# TrinketBlinkM0E.net
KiCad netlist of a schematic drawn in EAGLE
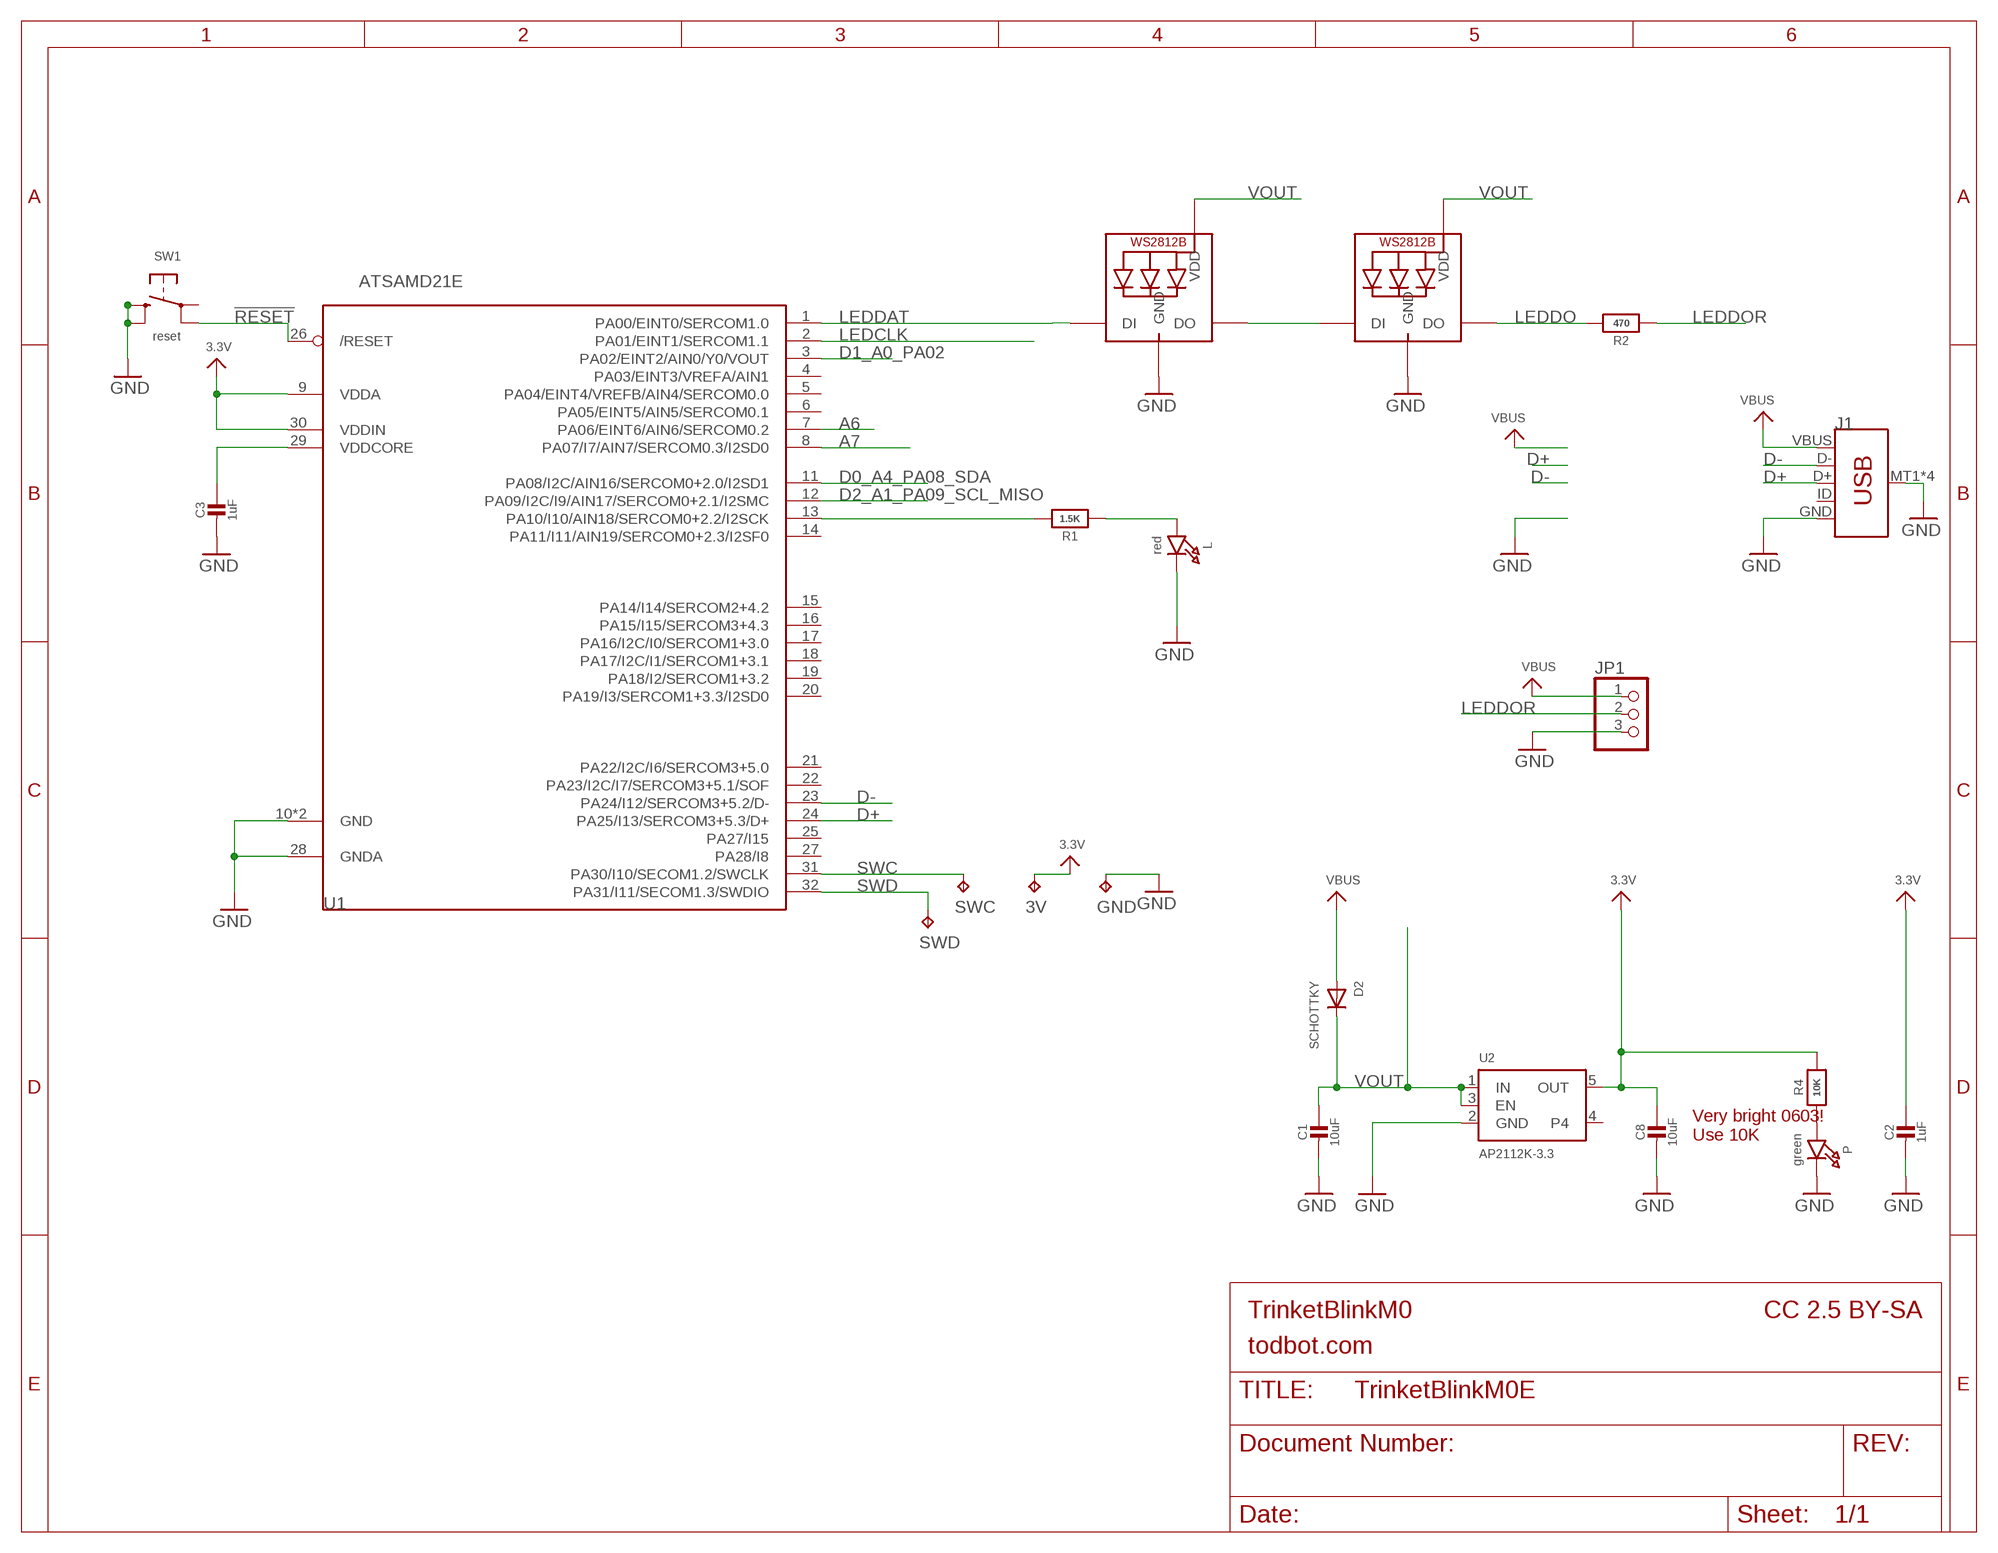
[diagram p0: schematic, sheet 1]

(export (version "E")
  (design (tool "Eeschema 10.0.6"))
  (components
    (comp (ref "3V")
      (value "TPB1,27")
      (footprint "eagle-import:B1,27")
      (libsource (lib "eagle-import") (part "TPB1,27"))
    )
    (comp (ref "C1")
      (value "10uF")
      (footprint "eagle-import:0805-NO")
      (libsource (lib "eagle-import") (part "CAP_CERAMIC0805-NOOUTLINE"))
    )
    (comp (ref "C2")
      (value "1uF")
      (footprint "eagle-import:0603-NO")
      (libsource (lib "eagle-import") (part "CAP_CERAMIC0603_NO"))
    )
    (comp (ref "C3")
      (value "1uF")
      (footprint "eagle-import:0603-NO")
      (libsource (lib "eagle-import") (part "CAP_CERAMIC0603_NO"))
    )
    (comp (ref "C8")
      (value "10uF")
      (footprint "eagle-import:0805-NO")
      (libsource (lib "eagle-import") (part "CAP_CERAMIC0805-NOOUTLINE"))
    )
    (comp (ref "D2")
      (value "SCHOTTKY")
      (footprint "eagle-import:SOD-123FL")
      (libsource (lib "eagle-import") (part "DIODE_SOD-123FL"))
    )
    (comp (ref "GND")
      (value "TPB1,27")
      (footprint "eagle-import:B1,27")
      (libsource (lib "eagle-import") (part "TPB1,27"))
    )
    (comp (ref "J1")
      (value "USB_MICRO-B_SMT")
      (footprint "eagle-import:USB-MICROB")
      (libsource (lib "eagle-import") (part "USB_MICRO-B_SMT"))
    )
    (comp (ref "JP1")
      (value "PINHD-1X3CB")
      (footprint "eagle-import:1X03-CLEANBIG")
      (libsource (lib "eagle-import") (part "PINHD-1X3CB"))
    )
    (comp (ref "L")
      (value "red")
      (footprint "eagle-import:CHIPLED_0603_NOOUTLINE")
      (libsource (lib "eagle-import") (part "LED0603_NOOUTLINE"))
    )
    (comp (ref "LED1")
      (value "WS2812B_5050N")
      (footprint "eagle-import:WS2812B-NARROW")
      (libsource (lib "eagle-import") (part "WS2812B_5050N"))
    )
    (comp (ref "LED2")
      (value "WS2812B_5050N")
      (footprint "eagle-import:WS2812B-NARROW")
      (libsource (lib "eagle-import") (part "WS2812B_5050N"))
    )
    (comp (ref "P")
      (value "green")
      (footprint "eagle-import:CHIPLED_0603_NOOUTLINE")
      (libsource (lib "eagle-import") (part "LED0603_NOOUTLINE"))
    )
    (comp (ref "R1")
      (value "1.5K")
      (footprint "eagle-import:0603-NO")
      (libsource (lib "eagle-import") (part "RESISTOR_0603_NOOUT"))
    )
    (comp (ref "R2")
      (value "470")
      (footprint "eagle-import:0603-NO")
      (libsource (lib "eagle-import") (part "RESISTOR_0603_NOOUT"))
    )
    (comp (ref "R4")
      (value "10K")
      (footprint "eagle-import:0603-NO")
      (libsource (lib "eagle-import") (part "RESISTOR_0603_NOOUT"))
    )
    (comp (ref "SW1")
      (value "reset")
      (footprint "eagle-import:BTN_KMR2_4.6X2.8")
      (libsource (lib "eagle-import") (part "SWITCH_TACT_SMT4.6X2.8"))
    )
    (comp (ref "SWC")
      (value "TPB1,27")
      (footprint "eagle-import:B1,27")
      (libsource (lib "eagle-import") (part "TPB1,27"))
    )
    (comp (ref "SWD")
      (value "TPB1,27")
      (footprint "eagle-import:B1,27")
      (libsource (lib "eagle-import") (part "TPB1,27"))
    )
    (comp (ref "U1")
      (value "ATSAMD21E")
      (footprint "eagle-import:QFN32_5MM")
      (libsource (lib "eagle-import") (part "ATSAMD21E"))
    )
    (comp (ref "U2")
      (value "AP2112K-3.3")
      (footprint "eagle-import:SOT23-5")
      (libsource (lib "eagle-import") (part "VREG_SOT23-5"))
    )
  )
  (nets
    (net (code "1") (name "/A6") (class "Default")
      (node (ref "U1") (pin "7") (pinfunction "PA06/EINT6/AIN6/SERCOM0.2_7") (pintype "bidirectional"))
    )
    (net (code "2") (name "/A7") (class "Default")
      (node (ref "U1") (pin "8") (pinfunction "PA07/I7/AIN7/SERCOM0.3/I2SD0_8") (pintype "bidirectional"))
    )
    (net (code "3") (name "/D+") (class "Default")
      (node (ref "J1") (pin "D+") (pinfunction "D+_D+") (pintype "bidirectional"))
      (node (ref "U1") (pin "24") (pinfunction "PA25/I13/SERCOM3+5.3/D+_24") (pintype "bidirectional"))
    )
    (net (code "4") (name "/D-") (class "Default")
      (node (ref "J1") (pin "D-") (pinfunction "D-_D-") (pintype "bidirectional"))
      (node (ref "U1") (pin "23") (pinfunction "PA24/I12/SERCOM3+5.2/D-_23") (pintype "bidirectional"))
    )
    (net (code "5") (name "/D0_A4_PA08_SDA") (class "Default")
      (node (ref "U1") (pin "11") (pinfunction "PA08/I2C/AIN16/SERCOM0+2.0/I2SD1_11") (pintype "bidirectional"))
    )
    (net (code "6") (name "/D1_A0_PA02") (class "Default")
      (node (ref "U1") (pin "3") (pinfunction "PA02/EINT2/AIN0/Y0/VOUT_3") (pintype "bidirectional"))
    )
    (net (code "7") (name "/D2_A1_PA09_SCL_MISO") (class "Default")
      (node (ref "U1") (pin "12") (pinfunction "PA09/I2C/I9/AIN17/SERCOM0+2.1/I2SMC_12") (pintype "bidirectional"))
    )
    (net (code "8") (name "/LEDCLK") (class "Default")
      (node (ref "U1") (pin "2") (pinfunction "PA01/EINT1/SERCOM1.1_2") (pintype "bidirectional"))
    )
    (net (code "9") (name "/LEDDAT") (class "Default")
      (node (ref "LED1") (pin "4-DIN") (pinfunction "DI_4-DIN") (pintype "input"))
      (node (ref "U1") (pin "1") (pinfunction "PA00/EINT0/SERCOM1.0_1") (pintype "bidirectional"))
    )
    (net (code "10") (name "/LEDDO") (class "Default")
      (node (ref "LED2") (pin "2-DOUT") (pinfunction "DO_2-DOUT") (pintype "output"))
      (node (ref "R2") (pin "2") (pinfunction "2_2") (pintype "passive"))
    )
    (net (code "11") (name "/LEDDOR") (class "Default")
      (node (ref "JP1") (pin "2") (pinfunction "2_2") (pintype "passive"))
      (node (ref "R2") (pin "1") (pinfunction "1_1") (pintype "passive"))
    )
    (net (code "12") (name "/SWC") (class "Default")
      (node (ref "SWC") (pin "TP") (pinfunction "TP_TP") (pintype "input"))
      (node (ref "U1") (pin "31") (pinfunction "PA30/I10/SECOM1.2/SWCLK_31") (pintype "bidirectional"))
    )
    (net (code "13") (name "/SWD") (class "Default")
      (node (ref "SWD") (pin "TP") (pinfunction "TP_TP") (pintype "input"))
      (node (ref "U1") (pin "32") (pinfunction "PA31/I11/SECOM1.3/SWDIO_32") (pintype "bidirectional"))
    )
    (net (code "14") (name "/VOUT") (class "Default")
      (node (ref "C1") (pin "1") (pinfunction "1_1") (pintype "passive"))
      (node (ref "D2") (pin "C") (pinfunction "C_C") (pintype "passive"))
      (node (ref "LED1") (pin "1-VDD") (pinfunction "VDD_1-VDD") (pintype "power_in"))
      (node (ref "LED2") (pin "1-VDD") (pinfunction "VDD_1-VDD") (pintype "power_in"))
      (node (ref "U2") (pin "1") (pinfunction "IN_1") (pintype "power_in"))
      (node (ref "U2") (pin "3") (pinfunction "EN_3") (pintype "input"))
    )
    (net (code "15") (name "/~{RESET}") (class "Default")
      (node (ref "SW1") (pin "A'") (pinfunction "P1_A'") (pintype "passive"))
      (node (ref "U1") (pin "26") (pinfunction "/RESET_26") (pintype "bidirectional"))
    )
    (net (code "16") (name "3.3V") (class "Default")
      (node (ref "3V") (pin "TP") (pinfunction "TP_TP") (pintype "input"))
      (node (ref "C2") (pin "1") (pinfunction "1_1") (pintype "passive"))
      (node (ref "C8") (pin "1") (pinfunction "1_1") (pintype "passive"))
      (node (ref "R4") (pin "2") (pinfunction "2_2") (pintype "passive"))
      (node (ref "U1") (pin "30") (pinfunction "VDDIN_30") (pintype "power_in"))
      (node (ref "U1") (pin "9") (pinfunction "VDDA_9") (pintype "power_in"))
      (node (ref "U2") (pin "5") (pinfunction "OUT_5") (pintype "power_in"))
    )
    (net (code "17") (name "GND") (class "Default")
      (node (ref "C1") (pin "2") (pinfunction "2_2") (pintype "passive"))
      (node (ref "C2") (pin "2") (pinfunction "2_2") (pintype "passive"))
      (node (ref "C3") (pin "2") (pinfunction "2_2") (pintype "passive"))
      (node (ref "C8") (pin "2") (pinfunction "2_2") (pintype "passive"))
      (node (ref "GND") (pin "TP") (pinfunction "TP_TP") (pintype "input"))
      (node (ref "J1") (pin "GND") (pinfunction "GND_GND") (pintype "power_in"))
      (node (ref "J1") (pin "MT1") (pinfunction "SHIELD_MT1") (pintype "bidirectional"))
      (node (ref "J1") (pin "MT2") (pinfunction "SHIELD_MT2") (pintype "bidirectional"))
      (node (ref "J1") (pin "P$1") (pinfunction "SHIELD_P$1") (pintype "bidirectional"))
      (node (ref "J1") (pin "P$2") (pinfunction "SHIELD_P$2") (pintype "bidirectional"))
      (node (ref "JP1") (pin "3") (pinfunction "3_3") (pintype "passive"))
      (node (ref "L") (pin "C") (pinfunction "C_C") (pintype "passive"))
      (node (ref "LED1") (pin "3-GND") (pinfunction "GND_3-GND") (pintype "power_in"))
      (node (ref "LED2") (pin "3-GND") (pinfunction "GND_3-GND") (pintype "power_in"))
      (node (ref "P") (pin "C") (pinfunction "C_C") (pintype "passive"))
      (node (ref "SW1") (pin "B") (pinfunction "S_B") (pintype "passive"))
      (node (ref "SW1") (pin "B'") (pinfunction "S1_B'") (pintype "passive"))
      (node (ref "U1") (pin "10") (pinfunction "GND_10") (pintype "power_in"))
      (node (ref "U1") (pin "28") (pinfunction "GNDA_28") (pintype "power_in"))
      (node (ref "U1") (pin "33") (pinfunction "GND_33") (pintype "power_in"))
      (node (ref "U2") (pin "2") (pinfunction "GND_2") (pintype "power_in"))
    )
    (net (code "18") (name "Net-(L-PadA)") (class "Default")
      (node (ref "L") (pin "A") (pinfunction "A_A") (pintype "passive"))
      (node (ref "R1") (pin "1") (pinfunction "1_1") (pintype "passive"))
    )
    (net (code "19") (name "Net-(LED1-DO)") (class "Default")
      (node (ref "LED1") (pin "2-DOUT") (pinfunction "DO_2-DOUT") (pintype "output"))
      (node (ref "LED2") (pin "4-DIN") (pinfunction "DI_4-DIN") (pintype "input"))
    )
    (net (code "20") (name "Net-(P-PadA)") (class "Default")
      (node (ref "P") (pin "A") (pinfunction "A_A") (pintype "passive"))
      (node (ref "R4") (pin "1") (pinfunction "1_1") (pintype "passive"))
    )
    (net (code "21") (name "Net-(U1-PA10{slash}I10{slash}AIN18{slash}SERCOM0+2.2{slash}I2SCK)") (class "Default")
      (node (ref "R1") (pin "2") (pinfunction "2_2") (pintype "passive"))
      (node (ref "U1") (pin "13") (pinfunction "PA10/I10/AIN18/SERCOM0+2.2/I2SCK_13") (pintype "bidirectional"))
    )
    (net (code "22") (name "Net-(U1-VDDCORE)") (class "Default")
      (node (ref "C3") (pin "1") (pinfunction "1_1") (pintype "passive"))
      (node (ref "U1") (pin "29") (pinfunction "VDDCORE_29") (pintype "power_in"))
    )
    (net (code "23") (name "VBUS") (class "Default")
      (node (ref "D2") (pin "A") (pinfunction "A_A") (pintype "passive"))
      (node (ref "J1") (pin "VBUS") (pinfunction "VBUS_VBUS") (pintype "power_in"))
      (node (ref "JP1") (pin "1") (pinfunction "1_1") (pintype "passive"))
    )
    (net (code "24") (name "unconnected-(J1-PadID)") (class "Default")
      (node (ref "J1") (pin "ID") (pinfunction "ID_ID") (pintype "bidirectional"))
    )
    (net (code "25") (name "unconnected-(SW1-P-PadA)") (class "Default")
      (node (ref "SW1") (pin "A") (pinfunction "P_A") (pintype "passive"))
    )
    (net (code "26") (name "unconnected-(U1-PA03{slash}EINT3{slash}VREFA{slash}AIN1-Pad4)") (class "Default")
      (node (ref "U1") (pin "4") (pinfunction "PA03/EINT3/VREFA/AIN1_4") (pintype "bidirectional"))
    )
    (net (code "27") (name "unconnected-(U1-PA04{slash}EINT4{slash}VREFB{slash}AIN4{slash}SERCOM0.0-Pad5)") (class "Default")
      (node (ref "U1") (pin "5") (pinfunction "PA04/EINT4/VREFB/AIN4/SERCOM0.0_5") (pintype "bidirectional"))
    )
    (net (code "28") (name "unconnected-(U1-PA05{slash}EINT5{slash}AIN5{slash}SERCOM0.1-Pad6)") (class "Default")
      (node (ref "U1") (pin "6") (pinfunction "PA05/EINT5/AIN5/SERCOM0.1_6") (pintype "bidirectional"))
    )
    (net (code "29") (name "unconnected-(U1-PA11{slash}I11{slash}AIN19{slash}SERCOM0+2.3{slash}I2SF0-Pad14)") (class "Default")
      (node (ref "U1") (pin "14") (pinfunction "PA11/I11/AIN19/SERCOM0+2.3/I2SF0_14") (pintype "bidirectional"))
    )
    (net (code "30") (name "unconnected-(U1-PA14{slash}I14{slash}SERCOM2+4.2-Pad15)") (class "Default")
      (node (ref "U1") (pin "15") (pinfunction "PA14/I14/SERCOM2+4.2_15") (pintype "bidirectional"))
    )
    (net (code "31") (name "unconnected-(U1-PA15{slash}I15{slash}SERCOM3+4.3-Pad16)") (class "Default")
      (node (ref "U1") (pin "16") (pinfunction "PA15/I15/SERCOM3+4.3_16") (pintype "bidirectional"))
    )
    (net (code "32") (name "unconnected-(U1-PA16{slash}I2C{slash}I0{slash}SERCOM1+3.0-Pad17)") (class "Default")
      (node (ref "U1") (pin "17") (pinfunction "PA16/I2C/I0/SERCOM1+3.0_17") (pintype "bidirectional"))
    )
    (net (code "33") (name "unconnected-(U1-PA17{slash}I2C{slash}I1{slash}SERCOM1+3.1-Pad18)") (class "Default")
      (node (ref "U1") (pin "18") (pinfunction "PA17/I2C/I1/SERCOM1+3.1_18") (pintype "bidirectional"))
    )
    (net (code "34") (name "unconnected-(U1-PA18{slash}I2{slash}SERCOM1+3.2-Pad19)") (class "Default")
      (node (ref "U1") (pin "19") (pinfunction "PA18/I2/SERCOM1+3.2_19") (pintype "bidirectional"))
    )
    (net (code "35") (name "unconnected-(U1-PA19{slash}I3{slash}SERCOM1+3.3{slash}I2SD0-Pad20)") (class "Default")
      (node (ref "U1") (pin "20") (pinfunction "PA19/I3/SERCOM1+3.3/I2SD0_20") (pintype "bidirectional"))
    )
    (net (code "36") (name "unconnected-(U1-PA22{slash}I2C{slash}I6{slash}SERCOM3+5.0-Pad21)") (class "Default")
      (node (ref "U1") (pin "21") (pinfunction "PA22/I2C/I6/SERCOM3+5.0_21") (pintype "bidirectional"))
    )
    (net (code "37") (name "unconnected-(U1-PA23{slash}I2C{slash}I7{slash}SERCOM3+5.1{slash}SOF-Pad22)") (class "Default")
      (node (ref "U1") (pin "22") (pinfunction "PA23/I2C/I7/SERCOM3+5.1/SOF_22") (pintype "bidirectional"))
    )
    (net (code "38") (name "unconnected-(U1-PA27{slash}I15-Pad25)") (class "Default")
      (node (ref "U1") (pin "25") (pinfunction "PA27/I15_25") (pintype "bidirectional"))
    )
    (net (code "39") (name "unconnected-(U1-PA28{slash}I8-Pad27)") (class "Default")
      (node (ref "U1") (pin "27") (pinfunction "PA28/I8_27") (pintype "bidirectional"))
    )
    (net (code "40") (name "unconnected-(U2-P4-Pad4)") (class "Default")
      (node (ref "U2") (pin "4") (pinfunction "P4_4") (pintype "bidirectional"))
    )
  )
)
